# Temperature_Sensing.net
KiCad netlist of a schematic drawn in Altium Designer
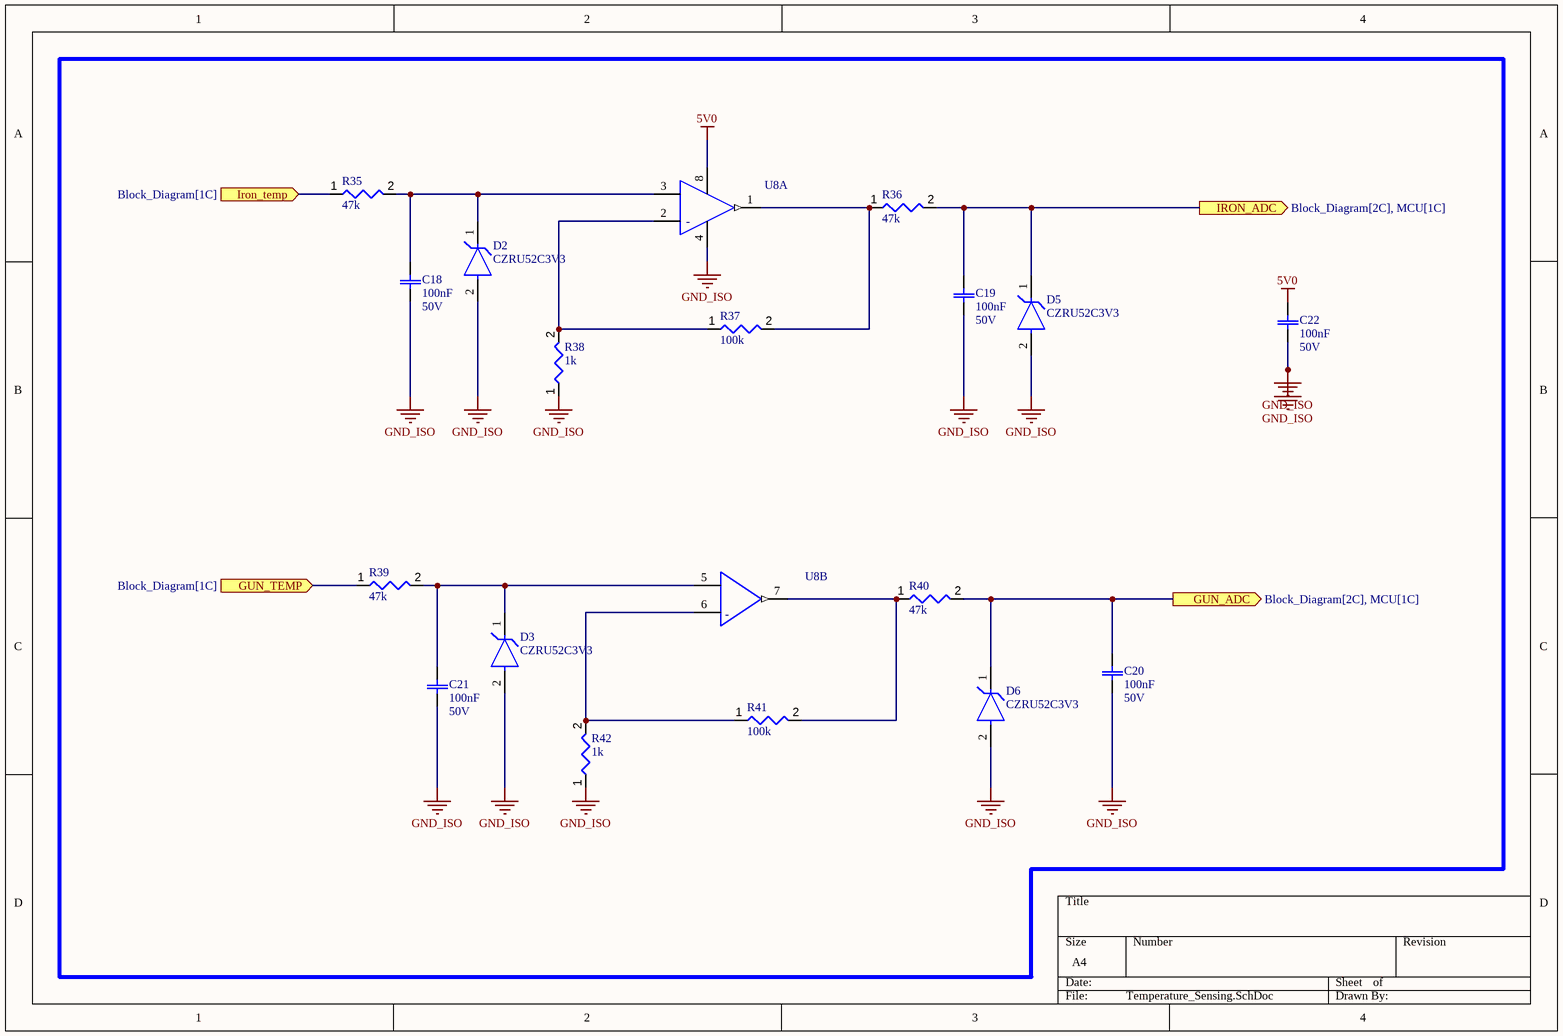
[diagram p0: Temperature_Sensing.SchDoc]

(export (version "E")
  (design (tool "Eeschema 10.0.6"))
  (components
    (comp (ref "C18")
      (value "100nF")
      (footprint "Generic Ceramic 0603 CAP")
      (fields
        (field (name "VOLTAGE RATING") "50V")
        (field (name "Comment") "CAP-MLCC_SMD-0603_MR-GCM_u_0.1uF_50V_10%_X8L")
      )
      (libsource (lib "Paulo Peixoto") (part "CAP_Ceramic"))
    )
    (comp (ref "C19")
      (value "100nF")
      (footprint "Generic Ceramic 0603 CAP")
      (fields
        (field (name "VOLTAGE RATING") "50V")
        (field (name "Comment") "CAP-MLCC_SMD-0603_MR-GCM_u_0.1uF_50V_10%_X8L")
      )
      (libsource (lib "Paulo Peixoto") (part "CAP_Ceramic"))
    )
    (comp (ref "C20")
      (value "100nF")
      (footprint "Generic Ceramic 0603 CAP")
      (fields
        (field (name "VOLTAGE RATING") "50V")
        (field (name "Comment") "CAP-MLCC_SMD-0603_MR-GCM_u_0.1uF_50V_10%_X8L")
      )
      (libsource (lib "Paulo Peixoto") (part "CAP_Ceramic"))
    )
    (comp (ref "C21")
      (value "100nF")
      (footprint "Generic Ceramic 0603 CAP")
      (fields
        (field (name "VOLTAGE RATING") "50V")
        (field (name "Comment") "CAP-MLCC_SMD-0603_MR-GCM_u_0.1uF_50V_10%_X8L")
      )
      (libsource (lib "Paulo Peixoto") (part "CAP_Ceramic"))
    )
    (comp (ref "C22")
      (value "100nF")
      (footprint "Generic Ceramic 0603 CAP")
      (fields
        (field (name "VOLTAGE RATING") "50V")
        (field (name "Comment") "CAP-MLCC_SMD-0603_MR-GCM_u_0.1uF_50V_10%_X8L")
      )
      (libsource (lib "Paulo Peixoto") (part "CAP_Ceramic"))
    )
    (comp (ref "D2")
      (value "CZRU52C3V3")
      (footprint "FP-0603-SOD-523F-MFG")
      (description "DIODE ZENER 3.3V 150MW 0603")
      (fields (field (name "TOLERANCE") "5%"))
      (libsource (lib "Altium Content Vault") (part "f813f71cba58e380607f5dd3caf9714"))
    )
    (comp (ref "D3")
      (value "CZRU52C3V3")
      (footprint "FP-0603-SOD-523F-MFG")
      (description "DIODE ZENER 3.3V 150MW 0603")
      (fields (field (name "TOLERANCE") "5%"))
      (libsource (lib "Altium Content Vault") (part "f813f71cba58e380607f5dd3caf9714"))
    )
    (comp (ref "D5")
      (value "CZRU52C3V3")
      (footprint "FP-0603-SOD-523F-MFG")
      (description "DIODE ZENER 3.3V 150MW 0603")
      (fields (field (name "TOLERANCE") "5%"))
      (libsource (lib "Altium Content Vault") (part "f813f71cba58e380607f5dd3caf9714"))
    )
    (comp (ref "D6")
      (value "CZRU52C3V3")
      (footprint "FP-0603-SOD-523F-MFG")
      (description "DIODE ZENER 3.3V 150MW 0603")
      (fields (field (name "TOLERANCE") "5%"))
      (libsource (lib "Altium Content Vault") (part "f813f71cba58e380607f5dd3caf9714"))
    )
    (comp (ref "R35")
      (value "47k")
      (footprint "Generic_0603_RES")
      (fields
        (field (name "TOLERANCE") "1%")
        (field (name "POWER") "100mW")
        (field (name "Comment") "RES-TK_SMD-0603_VIS-CRCW_K_47K_1/10W_1%")
      )
      (libsource (lib "Paulo Peixoto") (part "Res"))
    )
    (comp (ref "R36")
      (value "47k")
      (footprint "Generic_0603_RES")
      (fields
        (field (name "TOLERANCE") "1%")
        (field (name "POWER") "100mW")
        (field (name "Comment") "RES-TK_SMD-0603_VIS-CRCW_K_47K_1/10W_1%")
      )
      (libsource (lib "Paulo Peixoto") (part "Res"))
    )
    (comp (ref "R37")
      (value "100k")
      (footprint "Generic_0603_RES")
      (fields
        (field (name "POWER") "100mW")
        (field (name "TOLERANCE") "1%")
        (field (name "Comment") "RES-TK_SMD-0603_VIS-CRCW_K_100K_1/10W_1%")
      )
      (libsource (lib "Paulo Peixoto") (part "Res"))
    )
    (comp (ref "R38")
      (value "1k")
      (footprint "Generic_0603_RES")
      (fields
        (field (name "POWER") "100mW")
        (field (name "TOLERANCE") "1%")
        (field (name "Comment") "RES-TK_SMD-0603_VIS-CRCW_K_1K_1/10W_1%")
      )
      (libsource (lib "Paulo Peixoto") (part "Res"))
    )
    (comp (ref "R39")
      (value "47k")
      (footprint "Generic_0603_RES")
      (fields
        (field (name "TOLERANCE") "1%")
        (field (name "POWER") "100mW")
        (field (name "Comment") "RES-TK_SMD-0603_VIS-CRCW_K_47K_1/10W_1%")
      )
      (libsource (lib "Paulo Peixoto") (part "Res"))
    )
    (comp (ref "R40")
      (value "47k")
      (footprint "Generic_0603_RES")
      (fields
        (field (name "TOLERANCE") "1%")
        (field (name "POWER") "100mW")
        (field (name "Comment") "RES-TK_SMD-0603_VIS-CRCW_K_47K_1/10W_1%")
      )
      (libsource (lib "Paulo Peixoto") (part "Res"))
    )
    (comp (ref "R41")
      (value "100k")
      (footprint "Generic_0603_RES")
      (fields
        (field (name "POWER") "100mW")
        (field (name "TOLERANCE") "1%")
        (field (name "Comment") "RES-TK_SMD-0603_VIS-CRCW_K_100K_1/10W_1%")
      )
      (libsource (lib "Paulo Peixoto") (part "Res"))
    )
    (comp (ref "R42")
      (value "1k")
      (footprint "Generic_0603_RES")
      (fields
        (field (name "POWER") "100mW")
        (field (name "TOLERANCE") "1%")
        (field (name "Comment") "RES-TK_SMD-0603_VIS-CRCW_K_1K_1/10W_1%")
      )
      (libsource (lib "Paulo Peixoto") (part "Res"))
    )
    (comp (ref "U8")
      (value "LM358DR")
      (footprint "FP-D0008A-MFG")
      (description "IC OPAMP GP 2 CIRCUIT 8SOIC")
      (libsource (lib "Altium Content Vault") (part "0afdfe5f461d2cdd85604ff8654be97"))
    )
  )
  (nets
    (net (code "1") (name "/GUN_ADC") (class "Default")
      (node (ref "C20") (pin "2") (pinfunction "2_2") (pintype "passive"))
      (node (ref "D6") (pin "1") (pinfunction "C_1") (pintype "passive"))
      (node (ref "R40") (pin "2") (pinfunction "2_2") (pintype "passive"))
    )
    (net (code "2") (name "/GUN_TEMP") (class "Default")
      (node (ref "R39") (pin "1") (pinfunction "1_1") (pintype "passive"))
    )
    (net (code "3") (name "/IRON_ADC") (class "Default")
      (node (ref "C19") (pin "2") (pinfunction "2_2") (pintype "passive"))
      (node (ref "D5") (pin "1") (pinfunction "C_1") (pintype "passive"))
      (node (ref "R36") (pin "2") (pinfunction "2_2") (pintype "passive"))
    )
    (net (code "4") (name "/Iron_temp") (class "Default")
      (node (ref "R35") (pin "1") (pinfunction "1_1") (pintype "passive"))
    )
    (net (code "5") (name "5V0") (class "Default")
      (node (ref "C22") (pin "2") (pinfunction "2_2") (pintype "passive"))
      (node (ref "U8") (pin "8") (pinfunction "V+_8") (pintype "power_in"))
    )
    (net (code "6") (name "GND_ISO") (class "Default")
      (node (ref "C18") (pin "1") (pinfunction "1_1") (pintype "passive"))
      (node (ref "C19") (pin "1") (pinfunction "1_1") (pintype "passive"))
      (node (ref "C20") (pin "1") (pinfunction "1_1") (pintype "passive"))
      (node (ref "C21") (pin "1") (pinfunction "1_1") (pintype "passive"))
      (node (ref "C22") (pin "1") (pinfunction "1_1") (pintype "passive"))
      (node (ref "D2") (pin "2") (pinfunction "A_2") (pintype "passive"))
      (node (ref "D3") (pin "2") (pinfunction "A_2") (pintype "passive"))
      (node (ref "D5") (pin "2") (pinfunction "A_2") (pintype "passive"))
      (node (ref "D6") (pin "2") (pinfunction "A_2") (pintype "passive"))
      (node (ref "R38") (pin "1") (pinfunction "1_1") (pintype "passive"))
      (node (ref "R42") (pin "1") (pinfunction "1_1") (pintype "passive"))
      (node (ref "U8") (pin "4") (pinfunction "V-_4") (pintype "power_in"))
    )
    (net (code "7") (name "Net-(D2-C)") (class "Default")
      (node (ref "C18") (pin "2") (pinfunction "2_2") (pintype "passive"))
      (node (ref "D2") (pin "1") (pinfunction "C_1") (pintype "passive"))
      (node (ref "R35") (pin "2") (pinfunction "2_2") (pintype "passive"))
      (node (ref "U8") (pin "3") (pinfunction "IN1+_3") (pintype "tri_state"))
    )
    (net (code "8") (name "Net-(D3-C)") (class "Default")
      (node (ref "C21") (pin "2") (pinfunction "2_2") (pintype "passive"))
      (node (ref "D3") (pin "1") (pinfunction "C_1") (pintype "passive"))
      (node (ref "R39") (pin "2") (pinfunction "2_2") (pintype "passive"))
      (node (ref "U8") (pin "5") (pinfunction "IN2+_5") (pintype "tri_state"))
    )
    (net (code "9") (name "Net-(U8A-1OUT)") (class "Default")
      (node (ref "R36") (pin "1") (pinfunction "1_1") (pintype "passive"))
      (node (ref "R37") (pin "2") (pinfunction "2_2") (pintype "passive"))
      (node (ref "U8") (pin "1") (pinfunction "1OUT_1") (pintype "output"))
    )
    (net (code "10") (name "Net-(U8A-IN1-)") (class "Default")
      (node (ref "R37") (pin "1") (pinfunction "1_1") (pintype "passive"))
      (node (ref "R38") (pin "2") (pinfunction "2_2") (pintype "passive"))
      (node (ref "U8") (pin "2") (pinfunction "IN1-_2") (pintype "tri_state"))
    )
    (net (code "11") (name "Net-(U8B-2OUT)") (class "Default")
      (node (ref "R40") (pin "1") (pinfunction "1_1") (pintype "passive"))
      (node (ref "R41") (pin "2") (pinfunction "2_2") (pintype "passive"))
      (node (ref "U8") (pin "7") (pinfunction "2OUT_7") (pintype "output"))
    )
    (net (code "12") (name "Net-(U8B-IN2-)") (class "Default")
      (node (ref "R41") (pin "1") (pinfunction "1_1") (pintype "passive"))
      (node (ref "R42") (pin "2") (pinfunction "2_2") (pintype "passive"))
      (node (ref "U8") (pin "6") (pinfunction "IN2-_6") (pintype "tri_state"))
    )
  )
)
